# rail_crossing.net
KiCad netlist of a schematic drawn in EAGLE
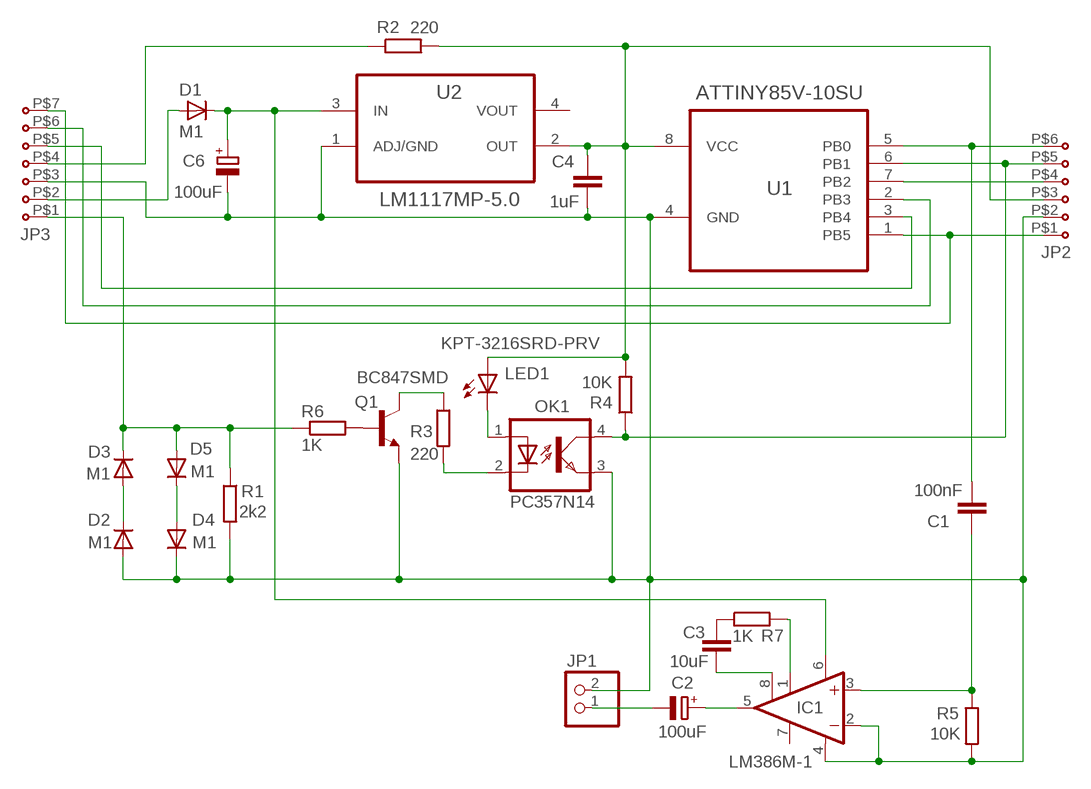
[diagram p0: schematic, sheet 1]

(export (version "E")
  (design (tool "Eeschema 10.0.6"))
  (components
    (comp (ref "C1")
      (value "100nF")
      (footprint "eagle-import:C1206")
      (libsource (lib "eagle-import") (part "C-EUC1206"))
    )
    (comp (ref "C2")
      (value "100uF")
      (footprint "eagle-import:SMC_C")
      (libsource (lib "eagle-import") (part "CPOL-EUSMCC"))
    )
    (comp (ref "C3")
      (value "10uF")
      (footprint "eagle-import:C1206")
      (libsource (lib "eagle-import") (part "C-EUC1206"))
    )
    (comp (ref "C4")
      (value "1uF")
      (footprint "eagle-import:C0402")
      (libsource (lib "eagle-import") (part "C-EUC0402"))
    )
    (comp (ref "C6")
      (value "100uF")
      (footprint "eagle-import:SMC_C")
      (libsource (lib "eagle-import") (part "CPOL-EUSMCC"))
    )
    (comp (ref "D1")
      (value "M1")
      (footprint "eagle-import:SMB")
      (libsource (lib "eagle-import") (part "ES2D"))
    )
    (comp (ref "D2")
      (value "M1")
      (footprint "eagle-import:SMB")
      (libsource (lib "eagle-import") (part "ES2D"))
    )
    (comp (ref "D3")
      (value "M1")
      (footprint "eagle-import:SMB")
      (libsource (lib "eagle-import") (part "ES2D"))
    )
    (comp (ref "D4")
      (value "M1")
      (footprint "eagle-import:SMB")
      (libsource (lib "eagle-import") (part "ES2D"))
    )
    (comp (ref "D5")
      (value "M1")
      (footprint "eagle-import:SMB")
      (libsource (lib "eagle-import") (part "ES2D"))
    )
    (comp (ref "IC1")
      (value "LM386M-1")
      (footprint "eagle-import:SO08")
      (libsource (lib "eagle-import") (part "LM386?-M1"))
    )
    (comp (ref "JP1")
      (value "PINHD-1X2/90")
      (footprint "eagle-import:1X02_90")
      (libsource (lib "eagle-import") (part "PINHD-1X2/90"))
    )
    (comp (ref "JP2")
      (value "J6SMD")
      (footprint "eagle-import:JP6SMD")
      (libsource (lib "eagle-import") (part "J6SMD"))
    )
    (comp (ref "JP3")
      (value "J7SMD")
      (footprint "eagle-import:JP7SMD")
      (libsource (lib "eagle-import") (part "J7SMD"))
    )
    (comp (ref "LED1")
      (value "KPT-3216SRD-PRV")
      (footprint "eagle-import:SML1206")
      (libsource (lib "eagle-import") (part "LEDSML1206"))
    )
    (comp (ref "OK1")
      (value "PC357N14")
      (footprint "eagle-import:SMD4")
      (libsource (lib "eagle-import") (part "LTV816S"))
    )
    (comp (ref "Q1")
      (value "BC847SMD")
      (footprint "eagle-import:SOT23")
      (libsource (lib "eagle-import") (part "BC847SMD"))
    )
    (comp (ref "R1")
      (value "2k2")
      (footprint "eagle-import:R1206")
      (libsource (lib "eagle-import") (part "R-EU_R1206"))
    )
    (comp (ref "R2")
      (value "220")
      (footprint "eagle-import:R1206")
      (libsource (lib "eagle-import") (part "R-EU_R1206"))
    )
    (comp (ref "R3")
      (value "220")
      (footprint "eagle-import:R1206")
      (libsource (lib "eagle-import") (part "R-EU_R1206"))
    )
    (comp (ref "R4")
      (value "10K")
      (footprint "eagle-import:R1206")
      (libsource (lib "eagle-import") (part "R-EU_R1206"))
    )
    (comp (ref "R5")
      (value "10K")
      (footprint "eagle-import:R1206")
      (libsource (lib "eagle-import") (part "R-EU_R1206"))
    )
    (comp (ref "R6")
      (value "1K")
      (footprint "eagle-import:R1206")
      (libsource (lib "eagle-import") (part "R-EU_R1206"))
    )
    (comp (ref "R7")
      (value "1K")
      (footprint "eagle-import:M1206")
      (libsource (lib "eagle-import") (part "R-EU_M1206"))
    )
    (comp (ref "U1")
      (value "ATTINY85V-10SU")
      (footprint "eagle-import:SOIC127P798X216-8N")
      (libsource (lib "eagle-import") (part "ATTINY85V-10SU"))
    )
    (comp (ref "U2")
      (value "LM1117MP-5.0")
      (footprint "eagle-import:SOT230P696X180-4N")
      (libsource (lib "eagle-import") (part "LM1117MP-5.0"))
    )
  )
  (nets
    (net (code "1") (name "Net-(C2-Pad-)") (class "Default")
      (node (ref "C2") (pin "-") (pinfunction "-_-") (pintype "passive"))
      (node (ref "JP1") (pin "1") (pinfunction "1_1") (pintype "passive"))
    )
    (net (code "2") (name "Net-(C3-Pad1)") (class "Default")
      (node (ref "C3") (pin "1") (pinfunction "1_1") (pintype "passive"))
      (node (ref "R7") (pin "1") (pinfunction "1_1") (pintype "passive"))
    )
    (net (code "3") (name "Net-(C3-Pad2)") (class "Default")
      (node (ref "C3") (pin "2") (pinfunction "2_2") (pintype "passive"))
      (node (ref "IC1") (pin "8") (pinfunction "GAIN_8") (pintype "passive"))
    )
    (net (code "4") (name "Net-(D2-PadC)") (class "Default")
      (node (ref "D2") (pin "C") (pinfunction "C_C") (pintype "passive"))
      (node (ref "D3") (pin "A") (pinfunction "A_A") (pintype "passive"))
    )
    (net (code "5") (name "Net-(D4-PadA)") (class "Default")
      (node (ref "D4") (pin "A") (pinfunction "A_A") (pintype "passive"))
      (node (ref "D5") (pin "C") (pinfunction "C_C") (pintype "passive"))
    )
    (net (code "6") (name "Net-(IC1-+IN)") (class "Default")
      (node (ref "C1") (pin "2") (pinfunction "2_2") (pintype "passive"))
      (node (ref "IC1") (pin "3") (pinfunction "+IN_3") (pintype "input"))
      (node (ref "R5") (pin "1") (pinfunction "1_1") (pintype "passive"))
    )
    (net (code "7") (name "Net-(IC1--IN)") (class "Default")
      (node (ref "C4") (pin "2") (pinfunction "2_2") (pintype "passive"))
      (node (ref "C6") (pin "-") (pinfunction "-_-") (pintype "passive"))
      (node (ref "D2") (pin "A") (pinfunction "A_A") (pintype "passive"))
      (node (ref "D4") (pin "C") (pinfunction "C_C") (pintype "passive"))
      (node (ref "IC1") (pin "2") (pinfunction "-IN_2") (pintype "input"))
      (node (ref "IC1") (pin "4") (pinfunction "GND_4") (pintype "power_in"))
      (node (ref "JP1") (pin "2") (pinfunction "2_2") (pintype "passive"))
      (node (ref "JP2") (pin "P$2") (pinfunction "2_P$2") (pintype "passive"))
      (node (ref "JP3") (pin "P$3") (pinfunction "3_P$3") (pintype "passive"))
      (node (ref "OK1") (pin "3") (pinfunction "EMIT_3") (pintype "passive"))
      (node (ref "Q1") (pin "2") (pinfunction "E_2") (pintype "passive"))
      (node (ref "R1") (pin "2") (pinfunction "2_2") (pintype "passive"))
      (node (ref "R5") (pin "2") (pinfunction "2_2") (pintype "passive"))
      (node (ref "U1") (pin "4") (pinfunction "GND_4") (pintype "passive"))
      (node (ref "U2") (pin "1") (pinfunction "ADJ/GND_1") (pintype "passive"))
    )
    (net (code "8") (name "Net-(IC1-GAIN-Pad1)") (class "Default")
      (node (ref "IC1") (pin "1") (pinfunction "GAIN_1") (pintype "passive"))
      (node (ref "R7") (pin "2") (pinfunction "2_2") (pintype "passive"))
    )
    (net (code "9") (name "Net-(IC1-OUT)") (class "Default")
      (node (ref "C2") (pin "+") (pinfunction "+_+") (pintype "passive"))
      (node (ref "IC1") (pin "5") (pinfunction "OUT_5") (pintype "output"))
    )
    (net (code "10") (name "Net-(IC1-VS)") (class "Default")
      (node (ref "C6") (pin "+") (pinfunction "+_+") (pintype "passive"))
      (node (ref "D1") (pin "C") (pinfunction "C_C") (pintype "passive"))
      (node (ref "IC1") (pin "6") (pinfunction "VS_6") (pintype "power_in"))
      (node (ref "U2") (pin "3") (pinfunction "IN_3") (pintype "input"))
    )
    (net (code "11") (name "Net-(JP2-1)") (class "Default")
      (node (ref "JP2") (pin "P$1") (pinfunction "1_P$1") (pintype "passive"))
      (node (ref "JP3") (pin "P$7") (pinfunction "7_P$7") (pintype "passive"))
      (node (ref "U1") (pin "1") (pinfunction "PB5_1") (pintype "bidirectional"))
    )
    (net (code "12") (name "Net-(JP2-3)") (class "Default")
      (node (ref "C4") (pin "1") (pinfunction "1_1") (pintype "passive"))
      (node (ref "JP2") (pin "P$3") (pinfunction "3_P$3") (pintype "passive"))
      (node (ref "LED1") (pin "A") (pinfunction "A_A") (pintype "passive"))
      (node (ref "R2") (pin "2") (pinfunction "2_2") (pintype "passive"))
      (node (ref "R4") (pin "2") (pinfunction "2_2") (pintype "passive"))
      (node (ref "U1") (pin "8") (pinfunction "VCC_8") (pintype "power_in"))
      (node (ref "U2") (pin "2") (pinfunction "OUT_2") (pintype "output"))
    )
    (net (code "13") (name "Net-(JP2-4)") (class "Default")
      (node (ref "JP2") (pin "P$4") (pinfunction "4_P$4") (pintype "passive"))
      (node (ref "U1") (pin "7") (pinfunction "PB2_7") (pintype "bidirectional"))
    )
    (net (code "14") (name "Net-(JP2-5)") (class "Default")
      (node (ref "JP2") (pin "P$5") (pinfunction "5_P$5") (pintype "passive"))
      (node (ref "OK1") (pin "4") (pinfunction "COL_4") (pintype "passive"))
      (node (ref "R4") (pin "1") (pinfunction "1_1") (pintype "passive"))
      (node (ref "U1") (pin "6") (pinfunction "PB1_6") (pintype "bidirectional"))
    )
    (net (code "15") (name "Net-(JP2-6)") (class "Default")
      (node (ref "C1") (pin "1") (pinfunction "1_1") (pintype "passive"))
      (node (ref "JP2") (pin "P$6") (pinfunction "6_P$6") (pintype "passive"))
      (node (ref "U1") (pin "5") (pinfunction "PB0_5") (pintype "bidirectional"))
    )
    (net (code "16") (name "Net-(JP3-1)") (class "Default")
      (node (ref "D3") (pin "C") (pinfunction "C_C") (pintype "passive"))
      (node (ref "D5") (pin "A") (pinfunction "A_A") (pintype "passive"))
      (node (ref "JP3") (pin "P$1") (pinfunction "1_P$1") (pintype "passive"))
      (node (ref "R1") (pin "1") (pinfunction "1_1") (pintype "passive"))
      (node (ref "R6") (pin "1") (pinfunction "1_1") (pintype "passive"))
    )
    (net (code "17") (name "Net-(JP3-2)") (class "Default")
      (node (ref "D1") (pin "A") (pinfunction "A_A") (pintype "passive"))
      (node (ref "JP3") (pin "P$2") (pinfunction "2_P$2") (pintype "passive"))
    )
    (net (code "18") (name "Net-(JP3-4)") (class "Default")
      (node (ref "JP3") (pin "P$4") (pinfunction "4_P$4") (pintype "passive"))
      (node (ref "R2") (pin "1") (pinfunction "1_1") (pintype "passive"))
    )
    (net (code "19") (name "Net-(JP3-5)") (class "Default")
      (node (ref "JP3") (pin "P$5") (pinfunction "5_P$5") (pintype "passive"))
      (node (ref "U1") (pin "3") (pinfunction "PB4_3") (pintype "bidirectional"))
    )
    (net (code "20") (name "Net-(JP3-6)") (class "Default")
      (node (ref "JP3") (pin "P$6") (pinfunction "6_P$6") (pintype "passive"))
      (node (ref "U1") (pin "2") (pinfunction "PB3_2") (pintype "bidirectional"))
    )
    (net (code "21") (name "Net-(OK1-A)") (class "Default")
      (node (ref "LED1") (pin "C") (pinfunction "C_C") (pintype "passive"))
      (node (ref "OK1") (pin "1") (pinfunction "A_1") (pintype "passive"))
    )
    (net (code "22") (name "Net-(OK1-C)") (class "Default")
      (node (ref "OK1") (pin "2") (pinfunction "C_2") (pintype "passive"))
      (node (ref "R3") (pin "2") (pinfunction "2_2") (pintype "passive"))
    )
    (net (code "23") (name "Net-(Q1-B)") (class "Default")
      (node (ref "Q1") (pin "1") (pinfunction "B_1") (pintype "passive"))
      (node (ref "R6") (pin "2") (pinfunction "2_2") (pintype "passive"))
    )
    (net (code "24") (name "Net-(Q1-C)") (class "Default")
      (node (ref "Q1") (pin "3") (pinfunction "C_3") (pintype "passive"))
      (node (ref "R3") (pin "1") (pinfunction "1_1") (pintype "passive"))
    )
    (net (code "25") (name "unconnected-(IC1-BYPASS-Pad7)") (class "Default")
      (node (ref "IC1") (pin "7") (pinfunction "BYPASS_7") (pintype "passive"))
    )
    (net (code "26") (name "unconnected-(U2-VOUT-Pad4)") (class "Default")
      (node (ref "U2") (pin "4") (pinfunction "VOUT_4") (pintype "output"))
    )
  )
)
